# pcb__2024-08-31.net
KiCad netlist of a schematic drawn in EasyEDA Pro
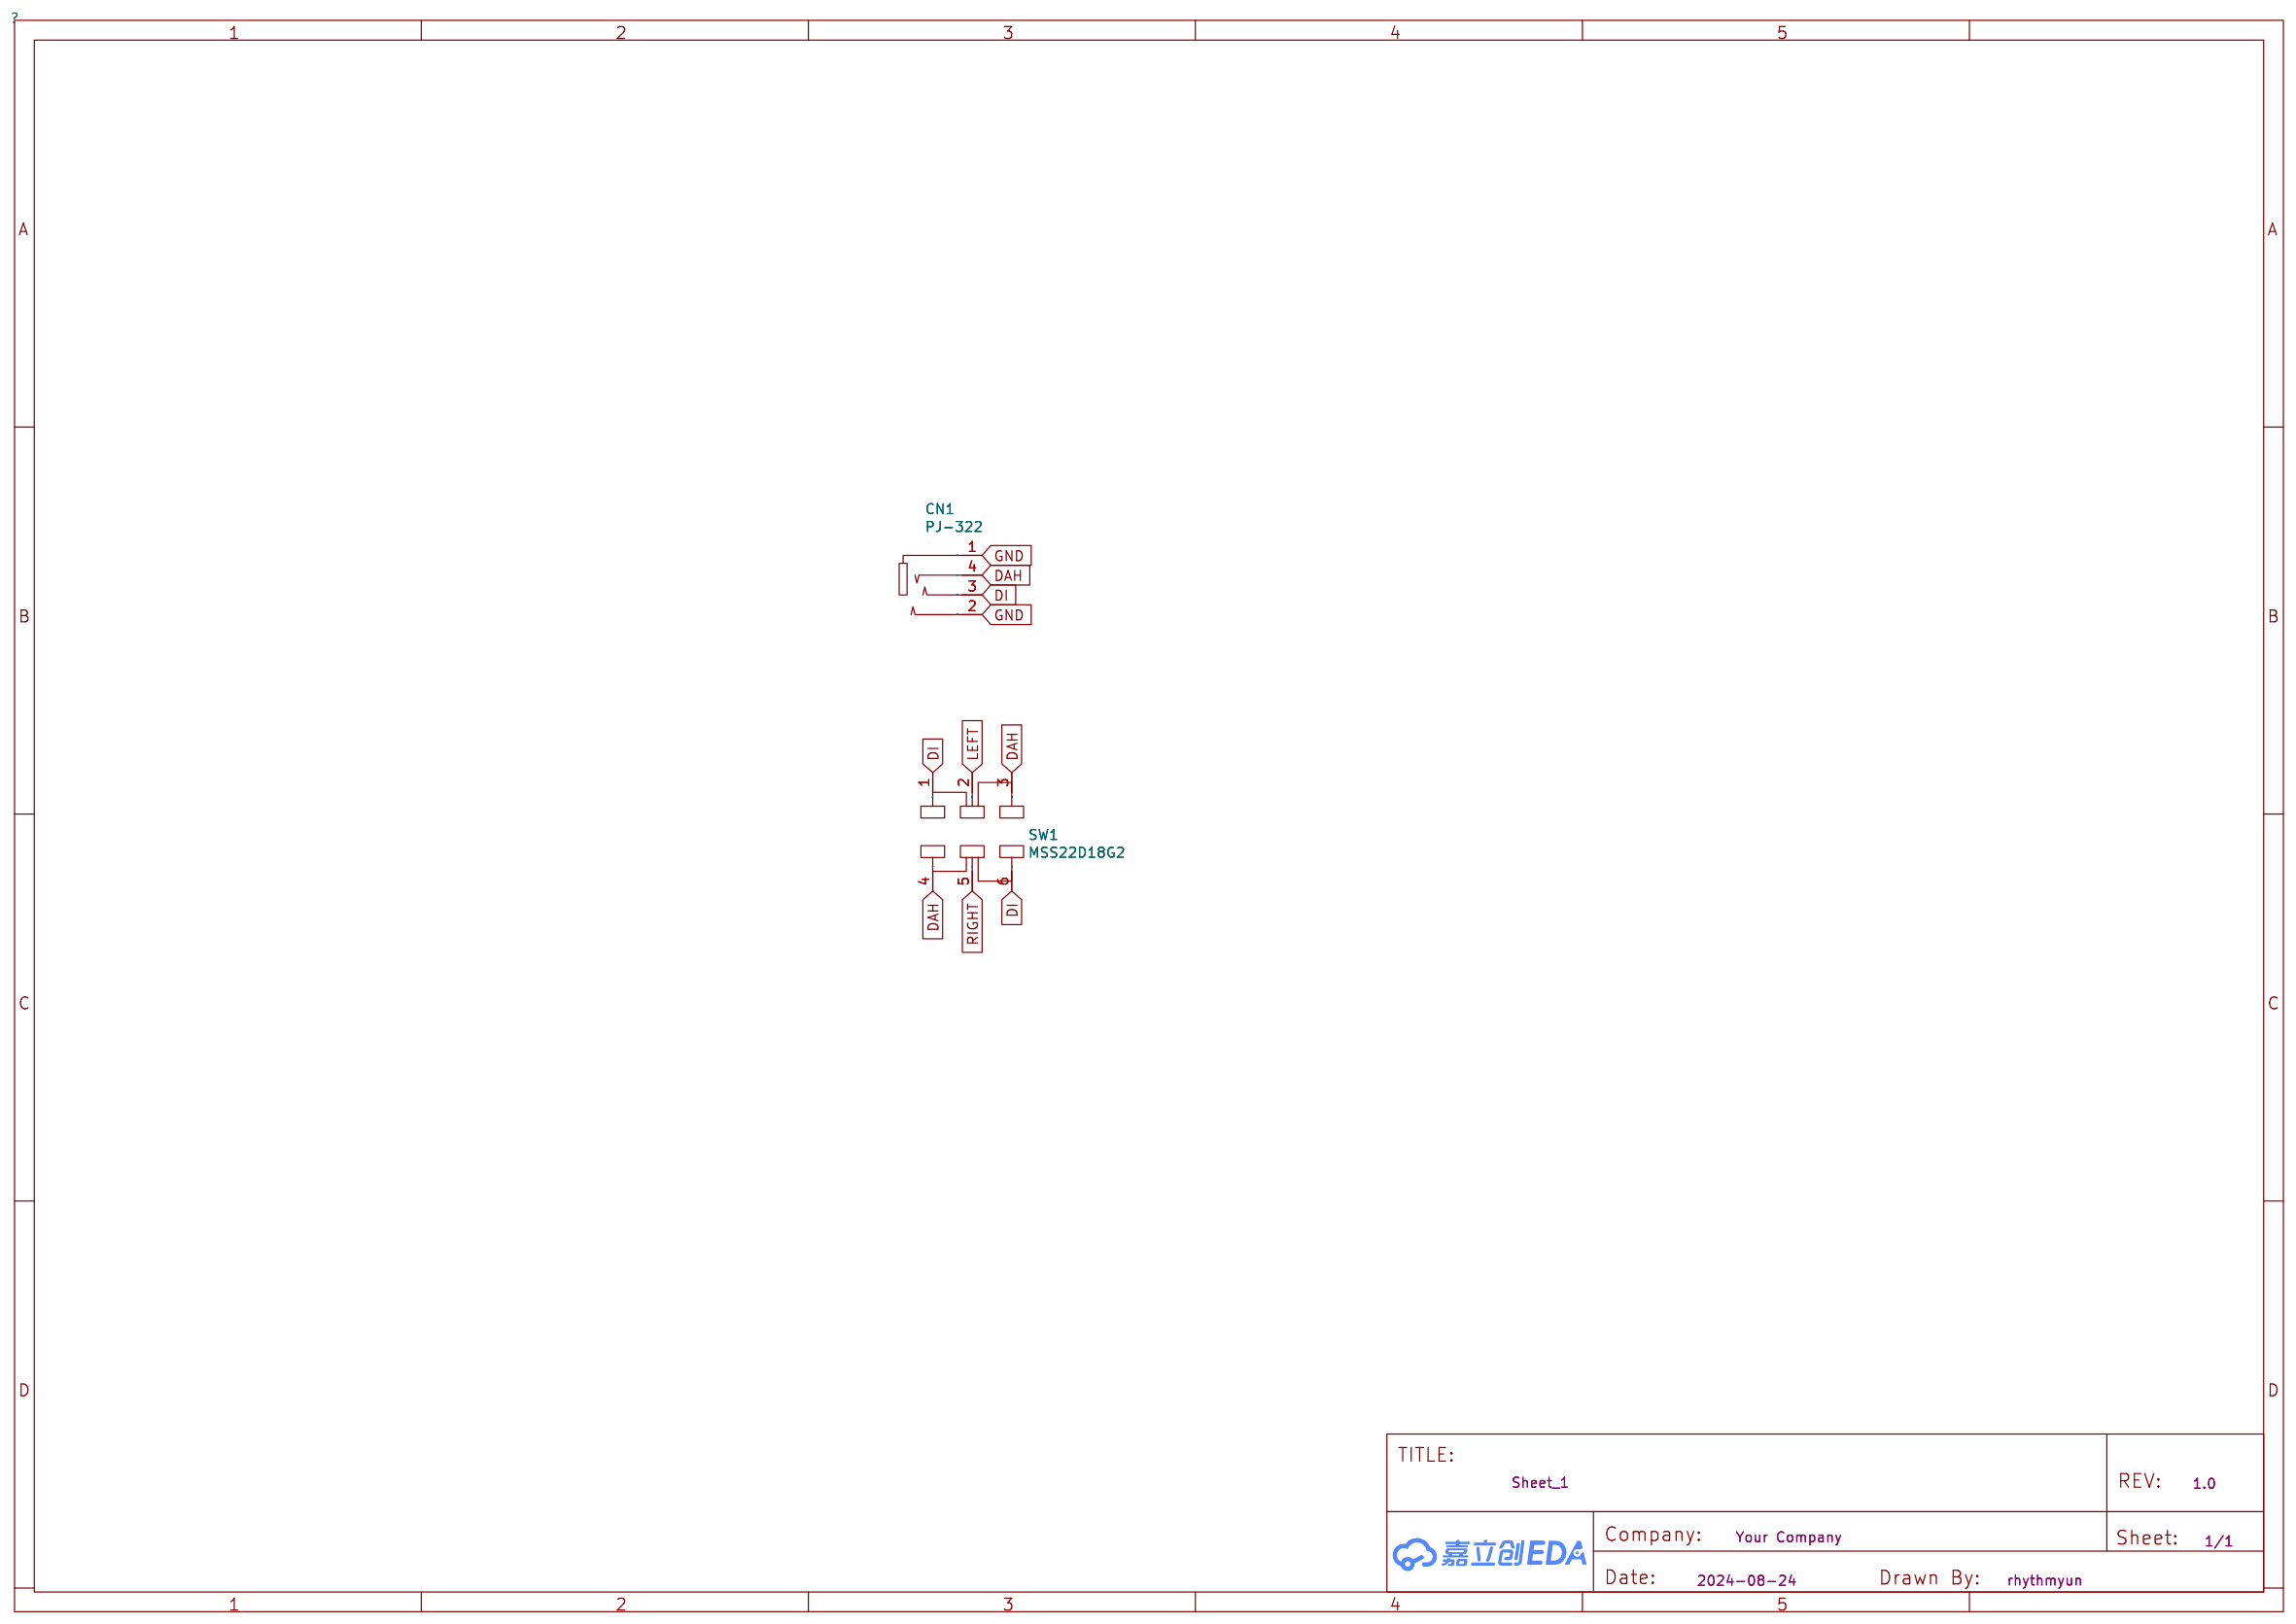
[diagram p0: schematic sheet]

(export (version "E")
  (design (tool "Eeschema 10.0.6"))
  (components
    (comp (ref "CN1")
      (value "PJ-322")
      (footprint "easyedapro:AUDIO-TH_HOOYA_PJ-322")
      (fields (field (name "Manufacturer Part") "PJ-322环保") (field (name "Manufacturer") "HOOYA(皓宇电子)"))
      (libsource (lib "easyedapro") (part "PJ-322"))
    )
    (comp (ref "SW1")
      (value "MSS22D18G2")
      (footprint "easyedapro:SW-TH_MSS22D18GX")
      (fields (field (name "Manufacturer") "SHOU HAN(首韩)"))
      (libsource (lib "easyedapro") (part "MSS22D18G2"))
    )
  )
  (nets
    (net (code "1") (name "DAH") (class "Default")
      (node (ref "CN1") (pin "4") (pinfunction "4_4") (pintype "unspecified"))
      (node (ref "SW1") (pin "3") (pinfunction "3_3") (pintype "unspecified"))
      (node (ref "SW1") (pin "4") (pinfunction "4_4") (pintype "unspecified"))
    )
    (net (code "2") (name "DI") (class "Default")
      (node (ref "CN1") (pin "3") (pinfunction "3_3") (pintype "unspecified"))
      (node (ref "SW1") (pin "1") (pinfunction "1_1") (pintype "unspecified"))
      (node (ref "SW1") (pin "6") (pinfunction "6_6") (pintype "unspecified"))
    )
    (net (code "3") (name "GND") (class "Default")
      (node (ref "CN1") (pin "1") (pinfunction "1_1") (pintype "unspecified"))
      (node (ref "CN1") (pin "2") (pinfunction "2_2") (pintype "unspecified"))
    )
    (net (code "4") (name "LEFT") (class "Default")
      (node (ref "SW1") (pin "2") (pinfunction "2_2") (pintype "unspecified"))
    )
    (net (code "5") (name "RIGHT") (class "Default")
      (node (ref "SW1") (pin "5") (pinfunction "5_5") (pintype "unspecified"))
    )
  )
)
